# 3_TopLevel.net
KiCad netlist of a schematic drawn in Altium Designer
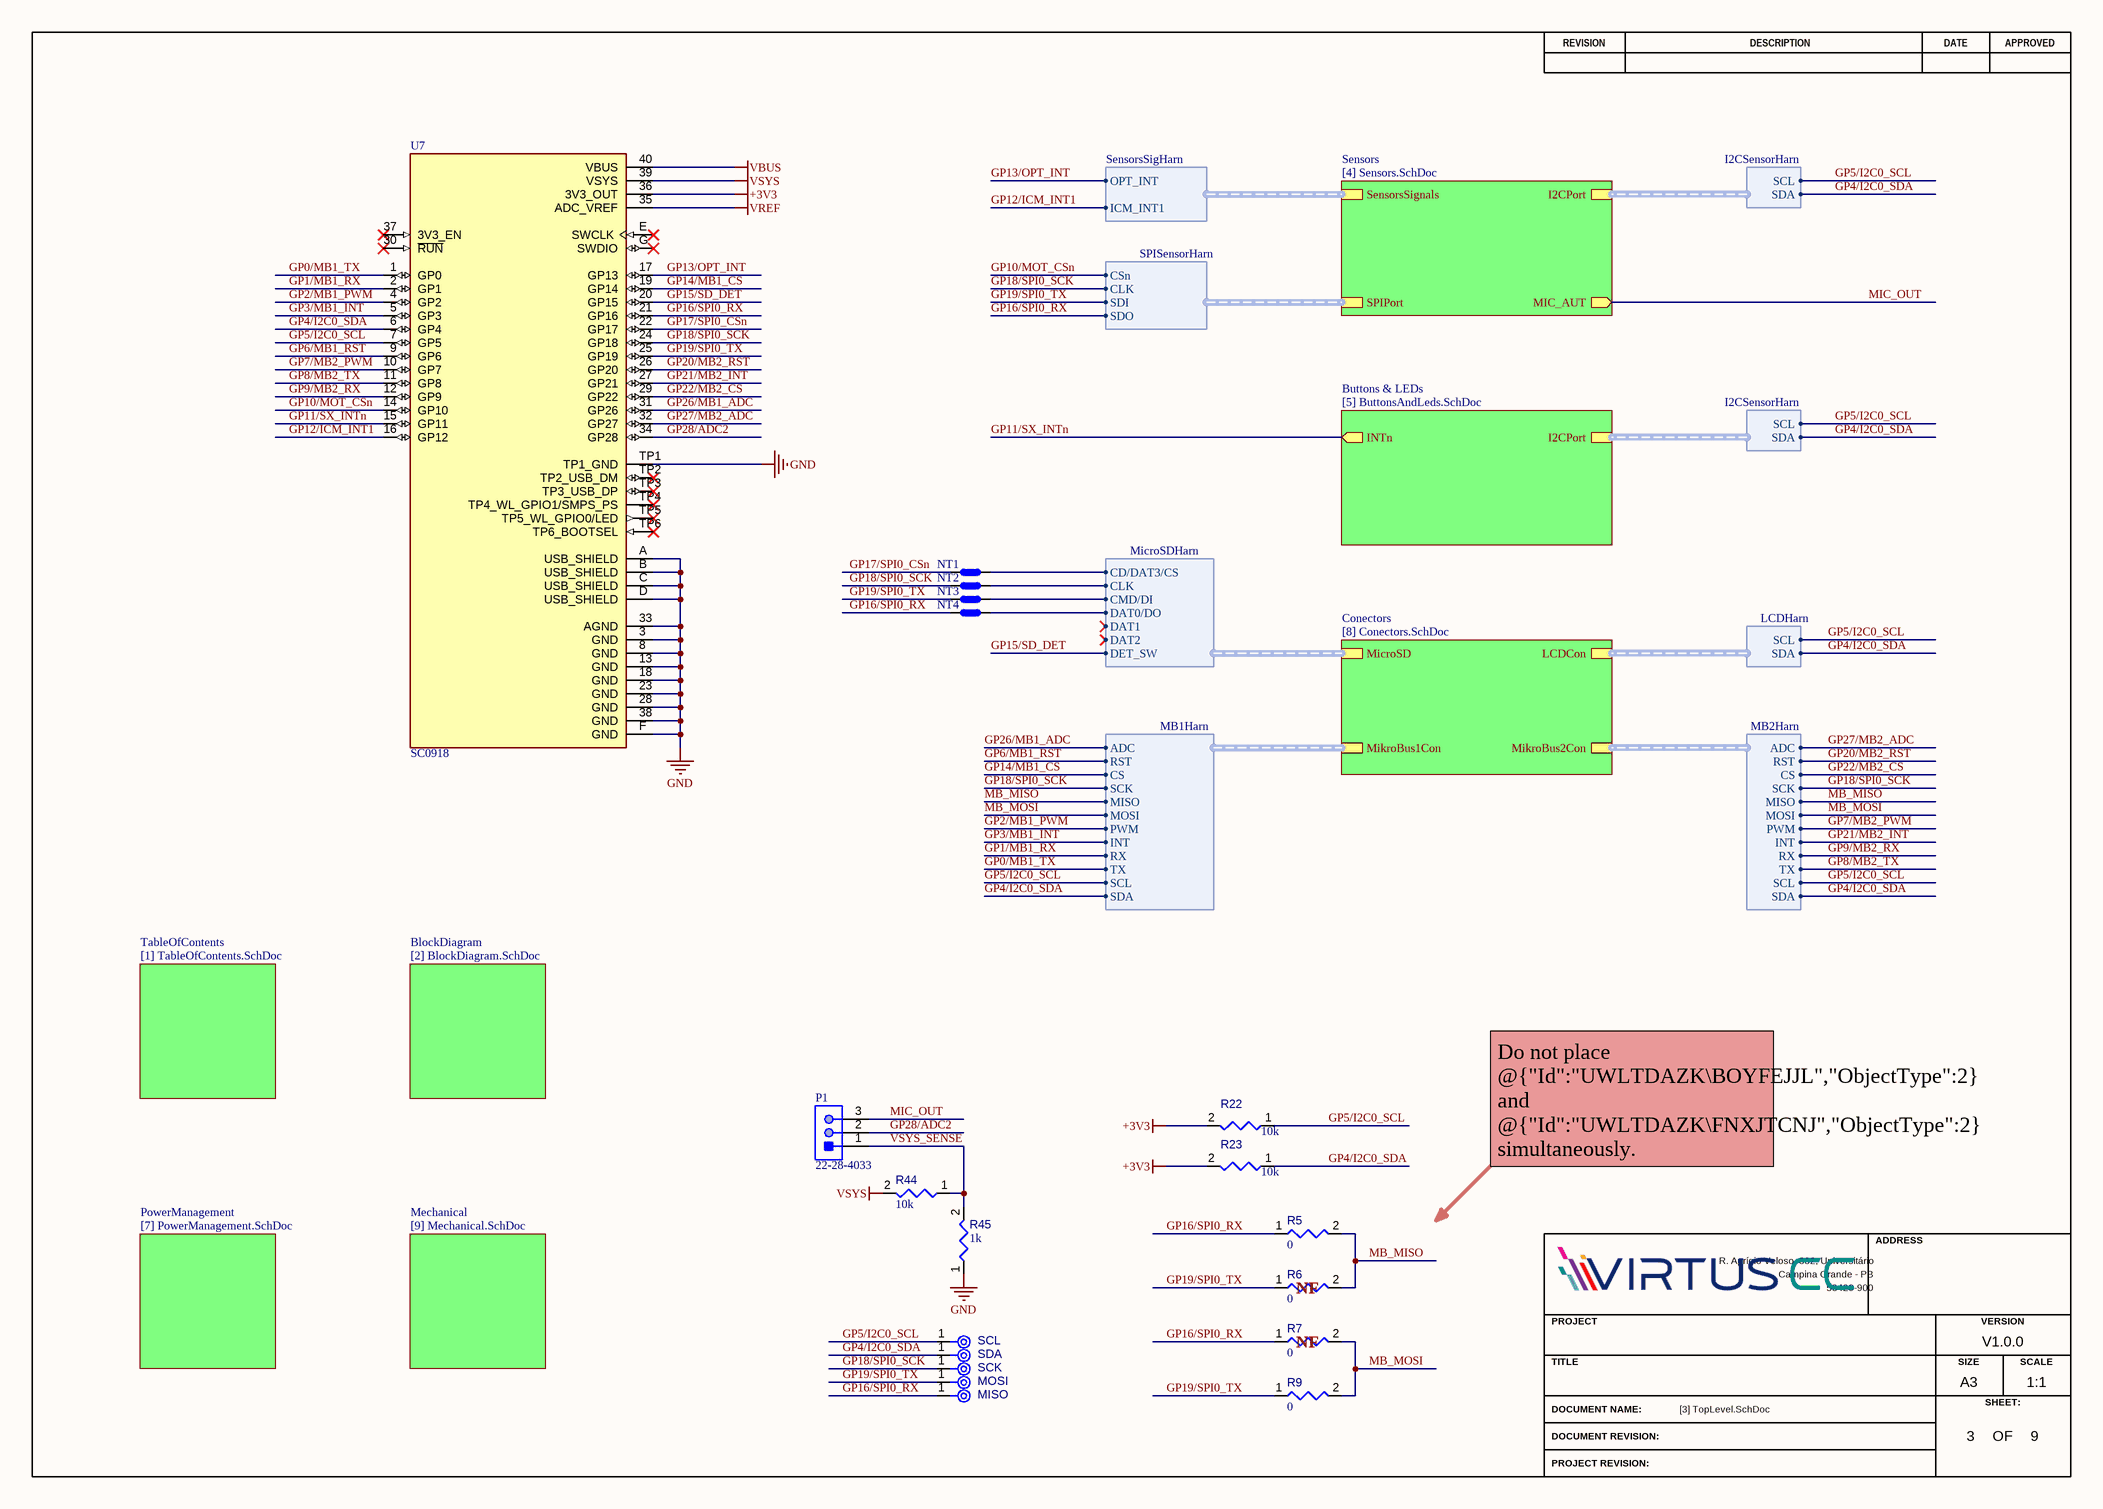
[diagram p0: [3] TopLevel.SchDoc]

(export (version "E")
  (design (tool "Eeschema 10.0.6"))
  (components
    (comp (ref "MISO")
      (value "TPAD6R")
      (footprint "TP06R")
      (description "0.6mm round")
      (libsource (lib "UFCG - Universidade Federal de Campina Grande") (part "CMP-001-0001-4"))
    )
    (comp (ref "MOSI")
      (value "TPAD6R")
      (footprint "TP06R")
      (description "0.6mm round")
      (libsource (lib "UFCG - Universidade Federal de Campina Grande") (part "CMP-001-0001-4"))
    )
    (comp (ref "NT1")
      (value "Net Tie")
      (footprint "New footprint 1")
      (description "Net Tie 0.3mm")
      (libsource (lib "UFCG - Universidade Federal de Campina Grande") (part "NetTie"))
    )
    (comp (ref "NT2")
      (value "Net Tie")
      (footprint "New footprint 1")
      (description "Net Tie 0.3mm")
      (libsource (lib "UFCG - Universidade Federal de Campina Grande") (part "NetTie"))
    )
    (comp (ref "NT3")
      (value "Net Tie")
      (footprint "New footprint 1")
      (description "Net Tie 0.3mm")
      (libsource (lib "UFCG - Universidade Federal de Campina Grande") (part "NetTie"))
    )
    (comp (ref "NT4")
      (value "Net Tie")
      (footprint "New footprint 1")
      (description "Net Tie 0.3mm")
      (libsource (lib "UFCG - Universidade Federal de Campina Grande") (part "NetTie"))
    )
    (comp (ref "P1")
      (value "22-28-4033")
      (footprint "MOLX-22-28-4033_V")
      (description "KK 254 Breakaway Header Vertical 3 Circuits 0.38um Gold Selective Plating Mating Pin 6.09mm")
      (libsource (lib "UFCG - Universidade Federal de Campina Grande") (part "CN-1P-M-R3"))
    )
    (comp (ref "R5")
      (value "0")
      (footprint "RESC0603(1608)_L")
      (description "Chip Resistor, 0 Ohm, 0.1 W, -55 to 155 degC, 0603 (1608 Metric)")
      (fields (field (name "TOLERANCE") "5%") (field (name "POWER") "100mW"))
      (libsource (lib "UFCG - Universidade Federal de Campina Grande") (part "RES-2"))
    )
    (comp (ref "R6")
      (value "0")
      (footprint "RESC0603(1608)_L")
      (description "Chip Resistor, 0 Ohm, 0.1 W, -55 to 155 degC, 0603 (1608 Metric)")
      (fields (field (name "TOLERANCE") "5%") (field (name "POWER") "100mW"))
      (libsource (lib "UFCG - Universidade Federal de Campina Grande") (part "RES-2"))
    )
    (comp (ref "R7")
      (value "0")
      (footprint "RESC0603(1608)_L")
      (description "Chip Resistor, 0 Ohm, 0.1 W, -55 to 155 degC, 0603 (1608 Metric)")
      (fields (field (name "TOLERANCE") "5%") (field (name "POWER") "100mW"))
      (libsource (lib "UFCG - Universidade Federal de Campina Grande") (part "RES-2"))
    )
    (comp (ref "R9")
      (value "0")
      (footprint "RESC0603(1608)_L")
      (description "Chip Resistor, 0 Ohm, 0.1 W, -55 to 155 degC, 0603 (1608 Metric)")
      (fields (field (name "TOLERANCE") "5%") (field (name "POWER") "100mW"))
      (libsource (lib "UFCG - Universidade Federal de Campina Grande") (part "RES-2"))
    )
    (comp (ref "R22")
      (value "10k")
      (footprint "RESC0603(1608)_L")
      (description "Chip Resistor, 10 KOhm, +/- 1%, 01 W, -55 to 155 degC, 0603 (1608 Metric)")
      (fields (field (name "POWER") "100mW") (field (name "TOLERANCE") "1%"))
      (libsource (lib "UFCG - Universidade Federal de Campina Grande") (part "RES-2"))
    )
    (comp (ref "R23")
      (value "10k")
      (footprint "RESC0603(1608)_L")
      (description "Chip Resistor, 10 KOhm, +/- 1%, 01 W, -55 to 155 degC, 0603 (1608 Metric)")
      (fields (field (name "POWER") "100mW") (field (name "TOLERANCE") "1%"))
      (libsource (lib "UFCG - Universidade Federal de Campina Grande") (part "RES-2"))
    )
    (comp (ref "R44")
      (value "10k")
      (footprint "RESC0603(1608)_L")
      (description "Chip Resistor, 10 KOhm, +/- 1%, 01 W, -55 to 155 degC, 0603 (1608 Metric)")
      (fields (field (name "POWER") "100mW") (field (name "TOLERANCE") "1%"))
      (libsource (lib "UFCG - Universidade Federal de Campina Grande") (part "RES-2"))
    )
    (comp (ref "R45")
      (value "1k")
      (footprint "RESC0603(1608)_L")
      (description "Chip Resistor, 1 KOhm, +/-1%, 0.1 W, -55 to 155 degC, 0603 (1608 Metric)")
      (fields (field (name "POWER") "100mW") (field (name "TOLERANCE") "1%"))
      (libsource (lib "UFCG - Universidade Federal de Campina Grande") (part "RES-2"))
    )
    (comp (ref "SCK")
      (value "TPAD6R")
      (footprint "TP06R")
      (description "0.6mm round")
      (libsource (lib "UFCG - Universidade Federal de Campina Grande") (part "CMP-001-0001-4"))
    )
    (comp (ref "SCL")
      (value "TPAD6R")
      (footprint "TP06R")
      (description "0.6mm round")
      (libsource (lib "UFCG - Universidade Federal de Campina Grande") (part "CMP-001-0001-4"))
    )
    (comp (ref "SDA")
      (value "TPAD6R")
      (footprint "TP06R")
      (description "0.6mm round")
      (libsource (lib "UFCG - Universidade Federal de Campina Grande") (part "CMP-001-0001-4"))
    )
    (comp (ref "U7")
      (value "SC0918")
      (footprint "MODULE_SC0918")
      (description "Raspberry Pi Pico W RP2040")
      (fields (field (name "MF") "Raspberry Pi"))
      (libsource (lib "UFCG - Universidade Federal de Campina Grande") (part "SC0918"))
    )
  )
  (nets
    (net (code "8") (name "+3V3") (class "Default")
      (node (ref "R22") (pin "2") (pinfunction "2_2") (pintype "passive"))
      (node (ref "R23") (pin "2") (pinfunction "2_2") (pintype "passive"))
      (node (ref "U7") (pin "36") (pinfunction "3V3_OUT_36") (pintype "power_in"))
    )
    (net (code "9") (name "/CD{slash}DAT3{slash}CS") (class "Default")
      (node (ref "NT1") (pin "2") (pintype "passive"))
    )
    (net (code "10") (name "/CMD{slash}DI") (class "Default")
      (node (ref "NT3") (pin "2") (pintype "passive"))
    )
    (net (code "11") (name "/DAT0{slash}DO") (class "Default")
      (node (ref "NT4") (pin "2") (pintype "passive"))
    )
    (net (code "12") (name "/GP0{slash}MB1_TX") (class "Default")
      (node (ref "U7") (pin "1") (pinfunction "GP0_1") (pintype "bidirectional"))
    )
    (net (code "13") (name "/GP1{slash}MB1_RX") (class "Default")
      (node (ref "U7") (pin "2") (pinfunction "GP1_2") (pintype "bidirectional"))
    )
    (net (code "14") (name "/GP2{slash}MB1_PWM") (class "Default")
      (node (ref "U7") (pin "4") (pinfunction "GP2_4") (pintype "bidirectional"))
    )
    (net (code "15") (name "/GP3{slash}MB1_INT") (class "Default")
      (node (ref "U7") (pin "5") (pinfunction "GP3_5") (pintype "bidirectional"))
    )
    (net (code "16") (name "/GP4{slash}I2C0_SDA") (class "Default")
      (node (ref "R23") (pin "1") (pinfunction "1_1") (pintype "passive"))
      (node (ref "SDA") (pin "1") (pinfunction "TP_1") (pintype "passive"))
      (node (ref "U7") (pin "6") (pinfunction "GP4_6") (pintype "bidirectional"))
    )
    (net (code "17") (name "/GP5{slash}I2C0_SCL") (class "Default")
      (node (ref "R22") (pin "1") (pinfunction "1_1") (pintype "passive"))
      (node (ref "SCL") (pin "1") (pinfunction "TP_1") (pintype "passive"))
      (node (ref "U7") (pin "7") (pinfunction "GP5_7") (pintype "bidirectional"))
    )
    (net (code "18") (name "/GP6{slash}MB1_RST") (class "Default")
      (node (ref "U7") (pin "9") (pinfunction "GP6_9") (pintype "bidirectional"))
    )
    (net (code "19") (name "/GP7{slash}MB2_PWM") (class "Default")
      (node (ref "U7") (pin "10") (pinfunction "GP7_10") (pintype "bidirectional"))
    )
    (net (code "20") (name "/GP8{slash}MB2_TX") (class "Default")
      (node (ref "U7") (pin "11") (pinfunction "GP8_11") (pintype "bidirectional"))
    )
    (net (code "21") (name "/GP9{slash}MB2_RX") (class "Default")
      (node (ref "U7") (pin "12") (pinfunction "GP9_12") (pintype "bidirectional"))
    )
    (net (code "22") (name "/GP10{slash}MOT_CSn") (class "Default")
      (node (ref "U7") (pin "14") (pinfunction "GP10_14") (pintype "bidirectional"))
    )
    (net (code "23") (name "/GP11{slash}SX_INTn") (class "Default")
      (node (ref "U7") (pin "15") (pinfunction "GP11_15") (pintype "bidirectional"))
    )
    (net (code "24") (name "/GP12{slash}ICM_INT1") (class "Default")
      (node (ref "U7") (pin "16") (pinfunction "GP12_16") (pintype "bidirectional"))
    )
    (net (code "25") (name "/GP13{slash}OPT_INT") (class "Default")
      (node (ref "U7") (pin "17") (pinfunction "GP13_17") (pintype "bidirectional"))
    )
    (net (code "26") (name "/GP14{slash}MB1_CS") (class "Default")
      (node (ref "U7") (pin "19") (pinfunction "GP14_19") (pintype "bidirectional"))
    )
    (net (code "27") (name "/GP15{slash}SD_DET") (class "Default")
      (node (ref "U7") (pin "20") (pinfunction "GP15_20") (pintype "bidirectional"))
    )
    (net (code "28") (name "/GP16{slash}SPI0_RX") (class "Default")
      (node (ref "MISO") (pin "1") (pinfunction "TP_1") (pintype "passive"))
      (node (ref "NT4") (pin "1") (pintype "passive"))
      (node (ref "R5") (pin "1") (pinfunction "1_1") (pintype "passive"))
      (node (ref "R7") (pin "1") (pinfunction "1_1") (pintype "passive"))
      (node (ref "U7") (pin "21") (pinfunction "GP16_21") (pintype "bidirectional"))
    )
    (net (code "29") (name "/GP17{slash}SPI0_CSn") (class "Default")
      (node (ref "NT1") (pin "1") (pintype "passive"))
      (node (ref "U7") (pin "22") (pinfunction "GP17_22") (pintype "bidirectional"))
    )
    (net (code "30") (name "/GP18{slash}SPI0_SCK") (class "Default")
      (node (ref "NT2") (pin "1") (pintype "passive"))
      (node (ref "SCK") (pin "1") (pinfunction "TP_1") (pintype "passive"))
      (node (ref "U7") (pin "24") (pinfunction "GP18_24") (pintype "bidirectional"))
    )
    (net (code "31") (name "/GP19{slash}SPI0_TX") (class "Default")
      (node (ref "MOSI") (pin "1") (pinfunction "TP_1") (pintype "passive"))
      (node (ref "NT3") (pin "1") (pintype "passive"))
      (node (ref "R6") (pin "1") (pinfunction "1_1") (pintype "passive"))
      (node (ref "R9") (pin "1") (pinfunction "1_1") (pintype "passive"))
      (node (ref "U7") (pin "25") (pinfunction "GP19_25") (pintype "bidirectional"))
    )
    (net (code "32") (name "/GP20{slash}MB2_RST") (class "Default")
      (node (ref "U7") (pin "26") (pinfunction "GP20_26") (pintype "bidirectional"))
    )
    (net (code "33") (name "/GP21{slash}MB2_INT") (class "Default")
      (node (ref "U7") (pin "27") (pinfunction "GP21_27") (pintype "bidirectional"))
    )
    (net (code "34") (name "/GP22{slash}MB2_CS") (class "Default")
      (node (ref "U7") (pin "29") (pinfunction "GP22_29") (pintype "bidirectional"))
    )
    (net (code "35") (name "/GP26{slash}MB1_ADC") (class "Default")
      (node (ref "U7") (pin "31") (pinfunction "GP26_31") (pintype "bidirectional"))
    )
    (net (code "36") (name "/GP27{slash}MB2_ADC") (class "Default")
      (node (ref "U7") (pin "32") (pinfunction "GP27_32") (pintype "bidirectional"))
    )
    (net (code "37") (name "/GP28{slash}ADC2") (class "Default")
      (node (ref "P1") (pin "2") (pinfunction "2_2") (pintype "passive"))
      (node (ref "U7") (pin "34") (pinfunction "GP28_34") (pintype "bidirectional"))
    )
    (net (code "38") (name "/MB_MISO") (class "Default")
      (node (ref "R5") (pin "2") (pinfunction "2_2") (pintype "passive"))
      (node (ref "R6") (pin "2") (pinfunction "2_2") (pintype "passive"))
    )
    (net (code "39") (name "/MB_MOSI") (class "Default")
      (node (ref "R7") (pin "2") (pinfunction "2_2") (pintype "passive"))
      (node (ref "R9") (pin "2") (pinfunction "2_2") (pintype "passive"))
    )
    (net (code "40") (name "/MIC_OUT") (class "Default")
      (node (ref "P1") (pin "3") (pinfunction "3_3") (pintype "passive"))
    )
    (net (code "41") (name "/VSYS_SENSE") (class "Default")
      (node (ref "P1") (pin "1") (pinfunction "1_1") (pintype "passive"))
      (node (ref "R44") (pin "1") (pinfunction "1_1") (pintype "passive"))
      (node (ref "R45") (pin "2") (pinfunction "2_2") (pintype "passive"))
    )
    (net (code "49") (name "GND") (class "Default")
      (node (ref "R45") (pin "1") (pinfunction "1_1") (pintype "passive"))
      (node (ref "U7") (pin "13") (pinfunction "GND_13") (pintype "power_in"))
      (node (ref "U7") (pin "18") (pinfunction "GND_18") (pintype "power_in"))
      (node (ref "U7") (pin "23") (pinfunction "GND_23") (pintype "power_in"))
      (node (ref "U7") (pin "28") (pinfunction "GND_28") (pintype "power_in"))
      (node (ref "U7") (pin "3") (pinfunction "GND_3") (pintype "power_in"))
      (node (ref "U7") (pin "33") (pinfunction "AGND_33") (pintype "power_in"))
      (node (ref "U7") (pin "38") (pinfunction "GND_38") (pintype "power_in"))
      (node (ref "U7") (pin "8") (pinfunction "GND_8") (pintype "power_in"))
      (node (ref "U7") (pin "A") (pinfunction "USB_SHIELD_A") (pintype "power_in"))
      (node (ref "U7") (pin "B") (pinfunction "USB_SHIELD_B") (pintype "power_in"))
      (node (ref "U7") (pin "C") (pinfunction "USB_SHIELD_C") (pintype "power_in"))
      (node (ref "U7") (pin "D") (pinfunction "USB_SHIELD_D") (pintype "power_in"))
      (node (ref "U7") (pin "F") (pinfunction "GND_F") (pintype "power_in"))
      (node (ref "U7") (pin "TP1") (pinfunction "TP1_GND_TP1") (pintype "power_in"))
    )
    (net (code "50") (name "VBUS") (class "Default")
      (node (ref "U7") (pin "40") (pinfunction "VBUS_40") (pintype "power_in"))
    )
    (net (code "51") (name "VREF") (class "Default")
      (node (ref "U7") (pin "35") (pinfunction "ADC_VREF_35") (pintype "power_in"))
    )
    (net (code "52") (name "VSYS") (class "Default")
      (node (ref "R44") (pin "2") (pinfunction "2_2") (pintype "passive"))
      (node (ref "U7") (pin "39") (pinfunction "VSYS_39") (pintype "power_in"))
    )
    (net (code "53") (name "unconnected-(NT2-Pad2)") (class "Default")
      (node (ref "NT2") (pin "2") (pintype "passive"))
    )
    (net (code "54") (name "unconnected-(U7-3V3_EN-Pad37)") (class "Default")
      (node (ref "U7") (pin "37") (pinfunction "3V3_EN_37") (pintype "input+no_connect"))
    )
    (net (code "55") (name "unconnected-(U7-SWCLK-PadE)") (class "Default")
      (node (ref "U7") (pin "E") (pinfunction "SWCLK_E") (pintype "input+no_connect"))
    )
    (net (code "56") (name "unconnected-(U7-SWDIO-PadG)") (class "Default")
      (node (ref "U7") (pin "G") (pinfunction "SWDIO_G") (pintype "bidirectional+no_connect"))
    )
    (net (code "57") (name "unconnected-(U7-TP2_USB_DM-PadTP2)") (class "Default")
      (node (ref "U7") (pin "TP2") (pinfunction "TP2_USB_DM_TP2") (pintype "bidirectional+no_connect"))
    )
    (net (code "58") (name "unconnected-(U7-TP3_USB_DP-PadTP3)") (class "Default")
      (node (ref "U7") (pin "TP3") (pinfunction "TP3_USB_DP_TP3") (pintype "bidirectional+no_connect"))
    )
    (net (code "59") (name "unconnected-(U7-TP4_WL_GPIO1{slash}SMPS_PS-PadTP4)") (class "Default")
      (node (ref "U7") (pin "TP4") (pinfunction "TP4_WL_GPIO1/SMPS_PS_TP4") (pintype "passive+no_connect"))
    )
    (net (code "60") (name "unconnected-(U7-TP5_WL_GPIO0{slash}LED-PadTP5)") (class "Default")
      (node (ref "U7") (pin "TP5") (pinfunction "TP5_WL_GPIO0/LED_TP5") (pintype "output+no_connect"))
    )
    (net (code "61") (name "unconnected-(U7-TP6_BOOTSEL-PadTP6)") (class "Default")
      (node (ref "U7") (pin "TP6") (pinfunction "TP6_BOOTSEL_TP6") (pintype "input+no_connect"))
    )
    (net (code "62") (name "unconnected-(U7-~{RUN}-Pad30)") (class "Default")
      (node (ref "U7") (pin "30") (pinfunction "~{RUN}_30") (pintype "input+no_connect"))
    )
  )
)
